# QSPI.net
KiCad netlist of a schematic drawn in Altium Designer
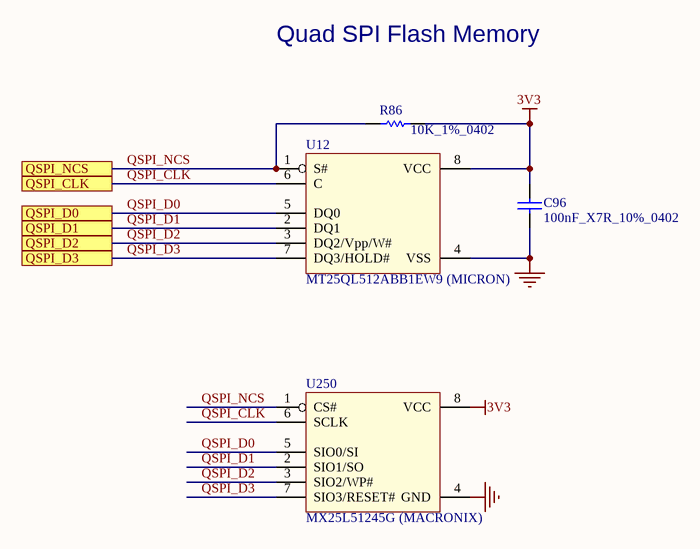
[diagram p0: QSPI.SchDoc]

(export (version "E")
  (design (tool "Eeschema 10.0.6"))
  (components
    (comp (ref "C96")
      (value "100nF_X7R_10%_0402")
      (footprint "0402C")
      (description "Capacitor,100nF,16V,X7R,10%,0402,YAGEO")
      (libsource (lib "MCD_TOOLS") (part "Cap_100nF_X7R_10%_0402"))
    )
    (comp (ref "R86")
      (value "10K_1%_0402")
      (footprint "0402R")
      (description "Resistor,10K,0402,1%,YAGEO")
      (libsource (lib "MCD_TOOLS") (part "Res_10K_1%_0402"))
    )
    (comp (ref "U12")
      (value "MT25QL512ABB1EW9 (MICRON)")
      (footprint "DFN8_1R27_6X8_TP4R8X5R16")
      (description "512Mb, 3V, Multiple I/O Serial Flash Memory, Quad/Dual")
      (libsource (lib "MCD_TOOLS_MISCELLANEOUS") (part "MT25QL512ABB1EW9"))
    )
    (comp (ref "U250")
      (value "MX25L51245G (MACRONIX)")
      (footprint "SON8_1R27_6X8")
      (description "512Mb, 3V, Multiple I/O Serial Flash Memory, Quad/Dual")
      (fields (field (name "PROVIDED") "Sub Co"))
      (libsource (lib "MCD_TOOLS_MISCELLANEOUS") (part "MX25L51245G"))
    )
  )
  (nets
    (net (code "1") (name "/QSPI_CLK") (class "Default")
      (node (ref "U12") (pin "6") (pinfunction "C_6") (pintype "passive"))
      (node (ref "U250") (pin "6") (pinfunction "SCLK_6") (pintype "passive"))
    )
    (net (code "2") (name "/QSPI_D0") (class "Default")
      (node (ref "U12") (pin "5") (pinfunction "DQ0_5") (pintype "passive"))
      (node (ref "U250") (pin "5") (pinfunction "SIO0/SI_5") (pintype "passive"))
    )
    (net (code "3") (name "/QSPI_D1") (class "Default")
      (node (ref "U12") (pin "2") (pinfunction "DQ1_2") (pintype "passive"))
      (node (ref "U250") (pin "2") (pinfunction "SIO1/SO_2") (pintype "passive"))
    )
    (net (code "4") (name "/QSPI_D2") (class "Default")
      (node (ref "U12") (pin "3") (pinfunction "DQ2/Vpp/W#_3") (pintype "passive"))
      (node (ref "U250") (pin "3") (pinfunction "SIO2/WP#_3") (pintype "passive"))
    )
    (net (code "5") (name "/QSPI_D3") (class "Default")
      (node (ref "U12") (pin "7") (pinfunction "DQ3/HOLD#_7") (pintype "passive"))
      (node (ref "U250") (pin "7") (pinfunction "SIO3/RESET#_7") (pintype "passive"))
    )
    (net (code "6") (name "/QSPI_NCS") (class "Default")
      (node (ref "R86") (pin "1") (pinfunction "1_1") (pintype "passive"))
      (node (ref "U12") (pin "1") (pinfunction "S#_1") (pintype "passive"))
      (node (ref "U250") (pin "1") (pinfunction "CS#_1") (pintype "passive"))
    )
    (net (code "7") (name "3V3") (class "Default")
      (node (ref "C96") (pin "2") (pinfunction "2_2") (pintype "passive"))
      (node (ref "R86") (pin "2") (pinfunction "2_2") (pintype "passive"))
      (node (ref "U12") (pin "8") (pinfunction "VCC_8") (pintype "passive"))
      (node (ref "U250") (pin "8") (pinfunction "VCC_8") (pintype "passive"))
    )
    (net (code "8") (name "GND") (class "Default")
      (node (ref "C96") (pin "1") (pinfunction "1_1") (pintype "passive"))
      (node (ref "U12") (pin "4") (pinfunction "VSS_4") (pintype "passive"))
      (node (ref "U250") (pin "4") (pinfunction "GND_4") (pintype "passive"))
    )
  )
)
